# CableAdapter.net
KiCad netlist of a schematic drawn in EAGLE
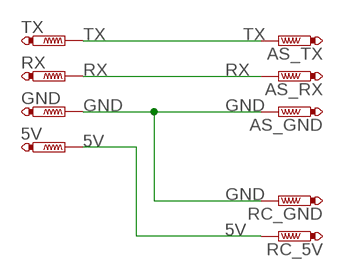
[diagram p0: schematic, sheet 1]

(export (version "E")
  (design (tool "Eeschema 10.0.6"))
  (components
    (comp (ref "5V")
      (value "PTR1TP20SQ")
      (footprint "eagle-import:TP20SQ")
      (libsource (lib "eagle-import") (part "PTR1TP20SQ"))
    )
    (comp (ref "AS_GND")
      (value "PTR1TP20SQ")
      (footprint "eagle-import:TP20SQ")
      (libsource (lib "eagle-import") (part "PTR1TP20SQ"))
    )
    (comp (ref "AS_RX")
      (value "PTR1TP20SQ")
      (footprint "eagle-import:TP20SQ")
      (libsource (lib "eagle-import") (part "PTR1TP20SQ"))
    )
    (comp (ref "AS_TX")
      (value "PTR1TP20SQ")
      (footprint "eagle-import:TP20SQ")
      (libsource (lib "eagle-import") (part "PTR1TP20SQ"))
    )
    (comp (ref "GND")
      (value "PTR1TP20SQ")
      (footprint "eagle-import:TP20SQ")
      (libsource (lib "eagle-import") (part "PTR1TP20SQ"))
    )
    (comp (ref "RC_5V")
      (value "PTR1TP20SQ")
      (footprint "eagle-import:TP20SQ")
      (libsource (lib "eagle-import") (part "PTR1TP20SQ"))
    )
    (comp (ref "RC_GND")
      (value "PTR1TP20SQ")
      (footprint "eagle-import:TP20SQ")
      (libsource (lib "eagle-import") (part "PTR1TP20SQ"))
    )
    (comp (ref "RX")
      (value "PTR1TP20SQ")
      (footprint "eagle-import:TP20SQ")
      (libsource (lib "eagle-import") (part "PTR1TP20SQ"))
    )
    (comp (ref "TX")
      (value "PTR1TP20SQ")
      (footprint "eagle-import:TP20SQ")
      (libsource (lib "eagle-import") (part "PTR1TP20SQ"))
    )
  )
  (nets
    (net (code "1") (name "/5V") (class "Default")
      (node (ref "5V") (pin "TP") (pinfunction "TP_TP") (pintype "input"))
      (node (ref "RC_5V") (pin "TP") (pinfunction "TP_TP") (pintype "input"))
    )
    (net (code "2") (name "/GND") (class "Default")
      (node (ref "AS_GND") (pin "TP") (pinfunction "TP_TP") (pintype "input"))
      (node (ref "GND") (pin "TP") (pinfunction "TP_TP") (pintype "input"))
      (node (ref "RC_GND") (pin "TP") (pinfunction "TP_TP") (pintype "input"))
    )
    (net (code "3") (name "/RX") (class "Default")
      (node (ref "AS_RX") (pin "TP") (pinfunction "TP_TP") (pintype "input"))
      (node (ref "RX") (pin "TP") (pinfunction "TP_TP") (pintype "input"))
    )
    (net (code "4") (name "/TX") (class "Default")
      (node (ref "AS_TX") (pin "TP") (pinfunction "TP_TP") (pintype "input"))
      (node (ref "TX") (pin "TP") (pinfunction "TP_TP") (pintype "input"))
    )
  )
)
